# ponteH.net
KiCad netlist of a schematic drawn in EAGLE
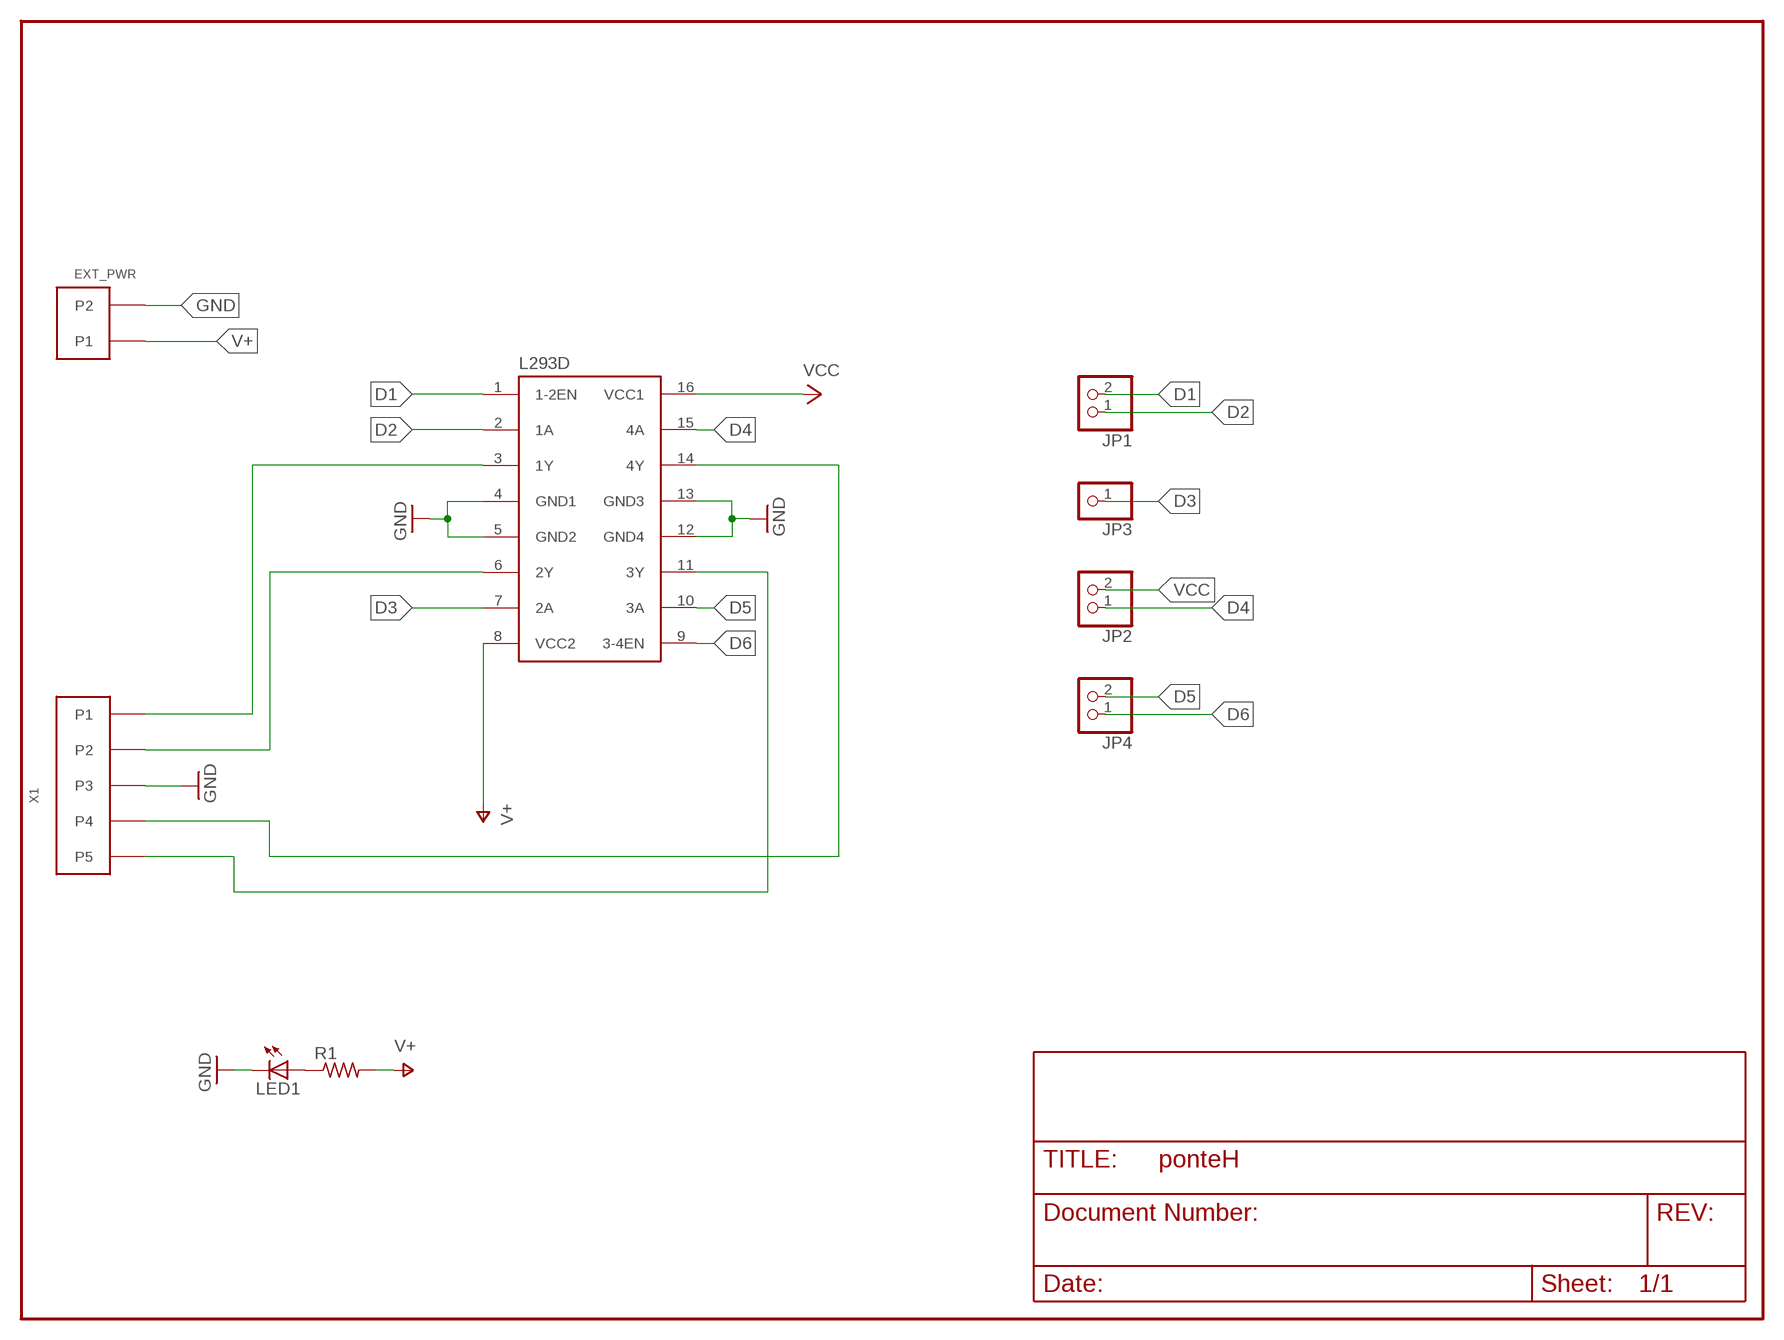
[diagram p0: schematic, sheet 1]

(export (version "E")
  (design (tool "Eeschema 10.0.6"))
  (components
    (comp (ref "EXT_PWR")
      (value "PINHEAD")
      (footprint "eagle-import:TERMBLOCK508")
      (libsource (lib "eagle-import") (part "PINHEAD"))
    )
    (comp (ref "JP1")
      (value "PINHD-1X2")
      (footprint "eagle-import:1X02")
      (libsource (lib "eagle-import") (part "PINHD-1X2"))
    )
    (comp (ref "JP2")
      (value "PINHD-1X2")
      (footprint "eagle-import:1X02")
      (libsource (lib "eagle-import") (part "PINHD-1X2"))
    )
    (comp (ref "JP3")
      (value "PINHD-1X1")
      (footprint "eagle-import:1X01")
      (libsource (lib "eagle-import") (part "PINHD-1X1"))
    )
    (comp (ref "JP4")
      (value "PINHD-1X2")
      (footprint "eagle-import:1X02")
      (libsource (lib "eagle-import") (part "PINHD-1X2"))
    )
    (comp (ref "L293D")
      (value "L293E")
      (footprint "eagle-import:DIL16")
      (libsource (lib "eagle-import") (part "L293E"))
    )
    (comp (ref "LED1")
      (value "LED3MM")
      (footprint "eagle-import:LED3MM")
      (libsource (lib "eagle-import") (part "LED3MM"))
    )
    (comp (ref "R1")
      (value "R-US_0207/10")
      (footprint "eagle-import:0207_10")
      (libsource (lib "eagle-import") (part "R-US_0207/10"))
    )
    (comp (ref "X1")
      (value "TERM5")
      (footprint "eagle-import:TERM1X5")
      (libsource (lib "eagle-import") (part "TERM5"))
    )
  )
  (nets
    (net (code "1") (name "D1") (class "Default")
      (node (ref "JP1") (pin "2") (pinfunction "2_2") (pintype "passive"))
      (node (ref "L293D") (pin "1") (pinfunction "1-2EN_1") (pintype "input"))
    )
    (net (code "2") (name "D2") (class "Default")
      (node (ref "JP1") (pin "1") (pinfunction "1_1") (pintype "passive"))
      (node (ref "L293D") (pin "2") (pinfunction "1A_2") (pintype "input"))
    )
    (net (code "3") (name "D3") (class "Default")
      (node (ref "JP3") (pin "1") (pinfunction "1_1") (pintype "passive"))
      (node (ref "L293D") (pin "7") (pinfunction "2A_7") (pintype "input"))
    )
    (net (code "4") (name "D4") (class "Default")
      (node (ref "JP2") (pin "1") (pinfunction "1_1") (pintype "passive"))
      (node (ref "L293D") (pin "15") (pinfunction "4A_15") (pintype "input"))
    )
    (net (code "5") (name "D5") (class "Default")
      (node (ref "JP4") (pin "2") (pinfunction "2_2") (pintype "passive"))
      (node (ref "L293D") (pin "10") (pinfunction "3A_10") (pintype "input"))
    )
    (net (code "6") (name "D6") (class "Default")
      (node (ref "JP4") (pin "1") (pinfunction "1_1") (pintype "passive"))
      (node (ref "L293D") (pin "9") (pinfunction "3-4EN_9") (pintype "input"))
    )
    (net (code "7") (name "GND") (class "Default")
      (node (ref "EXT_PWR") (pin "P$4") (pinfunction "P2_P$4") (pintype "bidirectional"))
      (node (ref "L293D") (pin "12") (pinfunction "GND4_12") (pintype "power_in"))
      (node (ref "L293D") (pin "13") (pinfunction "GND3_13") (pintype "power_in"))
      (node (ref "L293D") (pin "4") (pinfunction "GND1_4") (pintype "power_in"))
      (node (ref "L293D") (pin "5") (pinfunction "GND2_5") (pintype "power_in"))
      (node (ref "LED1") (pin "K") (pinfunction "C_K") (pintype "passive"))
      (node (ref "X1") (pin "P3") (pinfunction "P3_P3") (pintype "bidirectional"))
    )
    (net (code "8") (name "Net-(L293D-1Y)") (class "Default")
      (node (ref "L293D") (pin "3") (pinfunction "1Y_3") (pintype "output"))
      (node (ref "X1") (pin "P1") (pinfunction "P1_P1") (pintype "bidirectional"))
    )
    (net (code "9") (name "Net-(L293D-2Y)") (class "Default")
      (node (ref "L293D") (pin "6") (pinfunction "2Y_6") (pintype "output"))
      (node (ref "X1") (pin "P2") (pinfunction "P2_P2") (pintype "bidirectional"))
    )
    (net (code "10") (name "Net-(L293D-3Y)") (class "Default")
      (node (ref "L293D") (pin "11") (pinfunction "3Y_11") (pintype "output"))
      (node (ref "X1") (pin "P5") (pinfunction "P5_P5") (pintype "bidirectional"))
    )
    (net (code "11") (name "Net-(L293D-4Y)") (class "Default")
      (node (ref "L293D") (pin "14") (pinfunction "4Y_14") (pintype "output"))
      (node (ref "X1") (pin "P4") (pinfunction "P4_P4") (pintype "bidirectional"))
    )
    (net (code "12") (name "Net-(LED1-PadA)") (class "Default")
      (node (ref "LED1") (pin "A") (pinfunction "A_A") (pintype "passive"))
      (node (ref "R1") (pin "1") (pinfunction "1_1") (pintype "passive"))
    )
    (net (code "13") (name "V+") (class "Default")
      (node (ref "EXT_PWR") (pin "P$3") (pinfunction "P1_P$3") (pintype "bidirectional"))
      (node (ref "L293D") (pin "8") (pinfunction "VCC2_8") (pintype "power_in"))
      (node (ref "R1") (pin "2") (pinfunction "2_2") (pintype "passive"))
    )
    (net (code "14") (name "VCC") (class "Default")
      (node (ref "JP2") (pin "2") (pinfunction "2_2") (pintype "passive"))
      (node (ref "L293D") (pin "16") (pinfunction "VCC1_16") (pintype "power_in"))
    )
  )
)
